# L293D_MOTOR_S_R_C.net
KiCad netlist of a schematic drawn in EAGLE
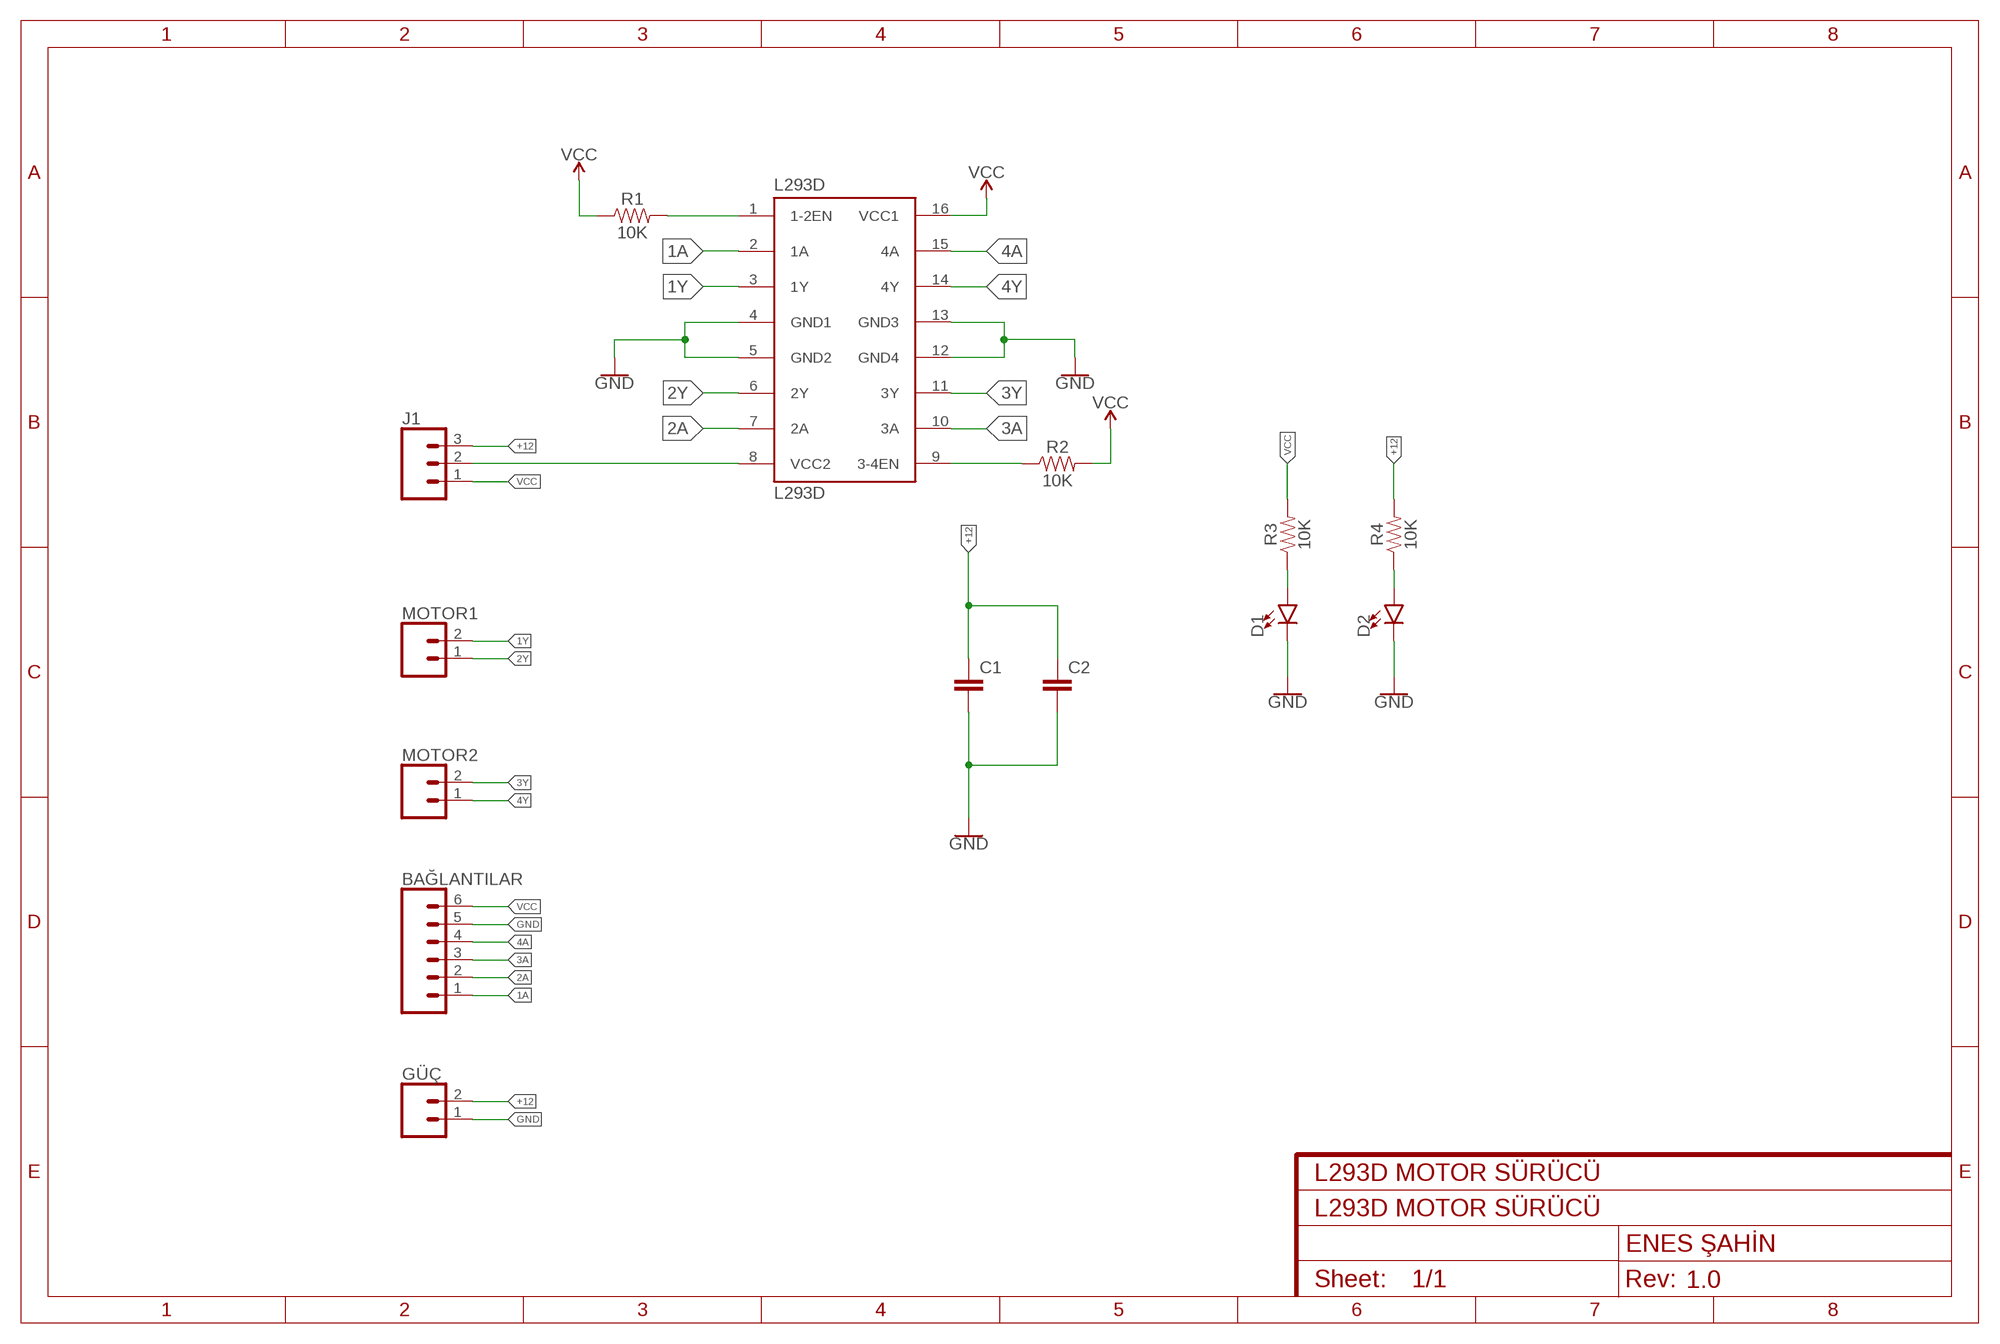
[diagram p0: schematic, sheet 1]

(export (version "E")
  (design (tool "Eeschema 10.0.6"))
  (components
    (comp (ref "BAĞLANTILAR")
      (value "CONN_06LOCK")
      (footprint "eagle-import:1X06_LOCK")
      (libsource (lib "eagle-import") (part "CONN_06LOCK"))
    )
    (comp (ref "C1")
      (value "C2,5-3")
      (footprint "eagle-import:C2.5-3")
      (libsource (lib "eagle-import") (part "C2,5-3"))
    )
    (comp (ref "C2")
      (value "C2,5-3")
      (footprint "eagle-import:C2.5-3")
      (libsource (lib "eagle-import") (part "C2,5-3"))
    )
    (comp (ref "D1")
      (value "LED-3MM-NO_SILK")
      (footprint "eagle-import:LED_3MM-NS")
      (libsource (lib "eagle-import") (part "LED-3MM-NO_SILK"))
    )
    (comp (ref "D2")
      (value "LED-3MM-NO_SILK")
      (footprint "eagle-import:LED_3MM-NS")
      (libsource (lib "eagle-import") (part "LED-3MM-NO_SILK"))
    )
    (comp (ref "GÜÇ")
      (value "CONN_02")
      (footprint "eagle-import:1X02")
      (libsource (lib "eagle-import") (part "CONN_02"))
    )
    (comp (ref "J1")
      (value "CONN_03")
      (footprint "eagle-import:1X03")
      (libsource (lib "eagle-import") (part "CONN_03"))
    )
    (comp (ref "L293D")
      (value "L293D")
      (footprint "eagle-import:DIL16")
      (libsource (lib "eagle-import") (part "L293D"))
    )
    (comp (ref "MOTOR1")
      (value "CONN_02")
      (footprint "eagle-import:1X02")
      (libsource (lib "eagle-import") (part "CONN_02"))
    )
    (comp (ref "MOTOR2")
      (value "CONN_02")
      (footprint "eagle-import:1X02")
      (libsource (lib "eagle-import") (part "CONN_02"))
    )
    (comp (ref "R1")
      (value "10K")
      (footprint "eagle-import:AXIAL-0.3")
      (libsource (lib "eagle-import") (part "1KOHM-HORIZ-1/4W-1%"))
    )
    (comp (ref "R2")
      (value "10K")
      (footprint "eagle-import:AXIAL-0.3")
      (libsource (lib "eagle-import") (part "1KOHM-HORIZ-1/4W-1%"))
    )
    (comp (ref "R3")
      (value "10K")
      (footprint "eagle-import:AXIAL-0.3")
      (libsource (lib "eagle-import") (part "1KOHM-HORIZ-1/4W-1%"))
    )
    (comp (ref "R4")
      (value "10K")
      (footprint "eagle-import:AXIAL-0.3")
      (libsource (lib "eagle-import") (part "1KOHM-HORIZ-1/4W-1%"))
    )
  )
  (nets
    (net (code "1") (name "+12") (class "Default")
      (node (ref "C1") (pin "1") (pinfunction "1_1") (pintype "passive"))
      (node (ref "C2") (pin "1") (pinfunction "1_1") (pintype "passive"))
      (node (ref "GÜÇ") (pin "2") (pinfunction "2_2") (pintype "passive"))
      (node (ref "J1") (pin "3") (pinfunction "3_3") (pintype "passive"))
      (node (ref "R4") (pin "P$2") (pinfunction "2_P$2") (pintype "passive"))
    )
    (net (code "2") (name "1A") (class "Default")
      (node (ref "BAĞLANTILAR") (pin "1") (pinfunction "1_1") (pintype "passive"))
      (node (ref "L293D") (pin "2") (pinfunction "1A_2") (pintype "input"))
    )
    (net (code "3") (name "1Y") (class "Default")
      (node (ref "L293D") (pin "3") (pinfunction "1Y_3") (pintype "output"))
      (node (ref "MOTOR1") (pin "2") (pinfunction "2_2") (pintype "passive"))
    )
    (net (code "4") (name "2A") (class "Default")
      (node (ref "BAĞLANTILAR") (pin "2") (pinfunction "2_2") (pintype "passive"))
      (node (ref "L293D") (pin "7") (pinfunction "2A_7") (pintype "input"))
    )
    (net (code "5") (name "2Y") (class "Default")
      (node (ref "L293D") (pin "6") (pinfunction "2Y_6") (pintype "output"))
      (node (ref "MOTOR1") (pin "1") (pinfunction "1_1") (pintype "passive"))
    )
    (net (code "6") (name "3A") (class "Default")
      (node (ref "BAĞLANTILAR") (pin "3") (pinfunction "3_3") (pintype "passive"))
      (node (ref "L293D") (pin "10") (pinfunction "3A_10") (pintype "input"))
    )
    (net (code "7") (name "3Y") (class "Default")
      (node (ref "L293D") (pin "11") (pinfunction "3Y_11") (pintype "output"))
      (node (ref "MOTOR2") (pin "2") (pinfunction "2_2") (pintype "passive"))
    )
    (net (code "8") (name "4A") (class "Default")
      (node (ref "BAĞLANTILAR") (pin "4") (pinfunction "4_4") (pintype "passive"))
      (node (ref "L293D") (pin "15") (pinfunction "4A_15") (pintype "input"))
    )
    (net (code "9") (name "4Y") (class "Default")
      (node (ref "L293D") (pin "14") (pinfunction "4Y_14") (pintype "output"))
      (node (ref "MOTOR2") (pin "1") (pinfunction "1_1") (pintype "passive"))
    )
    (net (code "10") (name "GND") (class "Default")
      (node (ref "BAĞLANTILAR") (pin "5") (pinfunction "5_5") (pintype "passive"))
      (node (ref "C1") (pin "2") (pinfunction "2_2") (pintype "passive"))
      (node (ref "C2") (pin "2") (pinfunction "2_2") (pintype "passive"))
      (node (ref "D1") (pin "K") (pinfunction "C_K") (pintype "passive"))
      (node (ref "D2") (pin "K") (pinfunction "C_K") (pintype "passive"))
      (node (ref "GÜÇ") (pin "1") (pinfunction "1_1") (pintype "passive"))
      (node (ref "L293D") (pin "12") (pinfunction "GND4_12") (pintype "power_in"))
      (node (ref "L293D") (pin "13") (pinfunction "GND3_13") (pintype "power_in"))
      (node (ref "L293D") (pin "4") (pinfunction "GND1_4") (pintype "power_in"))
      (node (ref "L293D") (pin "5") (pinfunction "GND2_5") (pintype "power_in"))
    )
    (net (code "11") (name "Net-(L293D-1-2EN)") (class "Default")
      (node (ref "L293D") (pin "1") (pinfunction "1-2EN_1") (pintype "input"))
      (node (ref "R1") (pin "P$2") (pinfunction "2_P$2") (pintype "passive"))
    )
    (net (code "12") (name "Net-(L293D-3-4EN)") (class "Default")
      (node (ref "L293D") (pin "9") (pinfunction "3-4EN_9") (pintype "input"))
      (node (ref "R2") (pin "P$1") (pinfunction "1_P$1") (pintype "passive"))
    )
    (net (code "13") (name "Net-(L293D-VCC2)") (class "Default")
      (node (ref "J1") (pin "2") (pinfunction "2_2") (pintype "passive"))
      (node (ref "L293D") (pin "8") (pinfunction "VCC2_8") (pintype "power_in"))
    )
    (net (code "14") (name "Net-(R3-1)") (class "Default")
      (node (ref "D1") (pin "A") (pinfunction "A_A") (pintype "passive"))
      (node (ref "R3") (pin "P$1") (pinfunction "1_P$1") (pintype "passive"))
    )
    (net (code "15") (name "Net-(R4-1)") (class "Default")
      (node (ref "D2") (pin "A") (pinfunction "A_A") (pintype "passive"))
      (node (ref "R4") (pin "P$1") (pinfunction "1_P$1") (pintype "passive"))
    )
    (net (code "16") (name "VCC") (class "Default")
      (node (ref "BAĞLANTILAR") (pin "6") (pinfunction "6_6") (pintype "passive"))
      (node (ref "J1") (pin "1") (pinfunction "1_1") (pintype "passive"))
      (node (ref "L293D") (pin "16") (pinfunction "VCC1_16") (pintype "power_in"))
      (node (ref "R1") (pin "P$1") (pinfunction "1_P$1") (pintype "passive"))
      (node (ref "R2") (pin "P$2") (pinfunction "2_P$2") (pintype "passive"))
      (node (ref "R3") (pin "P$2") (pinfunction "2_P$2") (pintype "passive"))
    )
  )
)
